# krajBB-Moj_i__Matej2_2.net
KiCad netlist of a schematic drawn in EAGLE
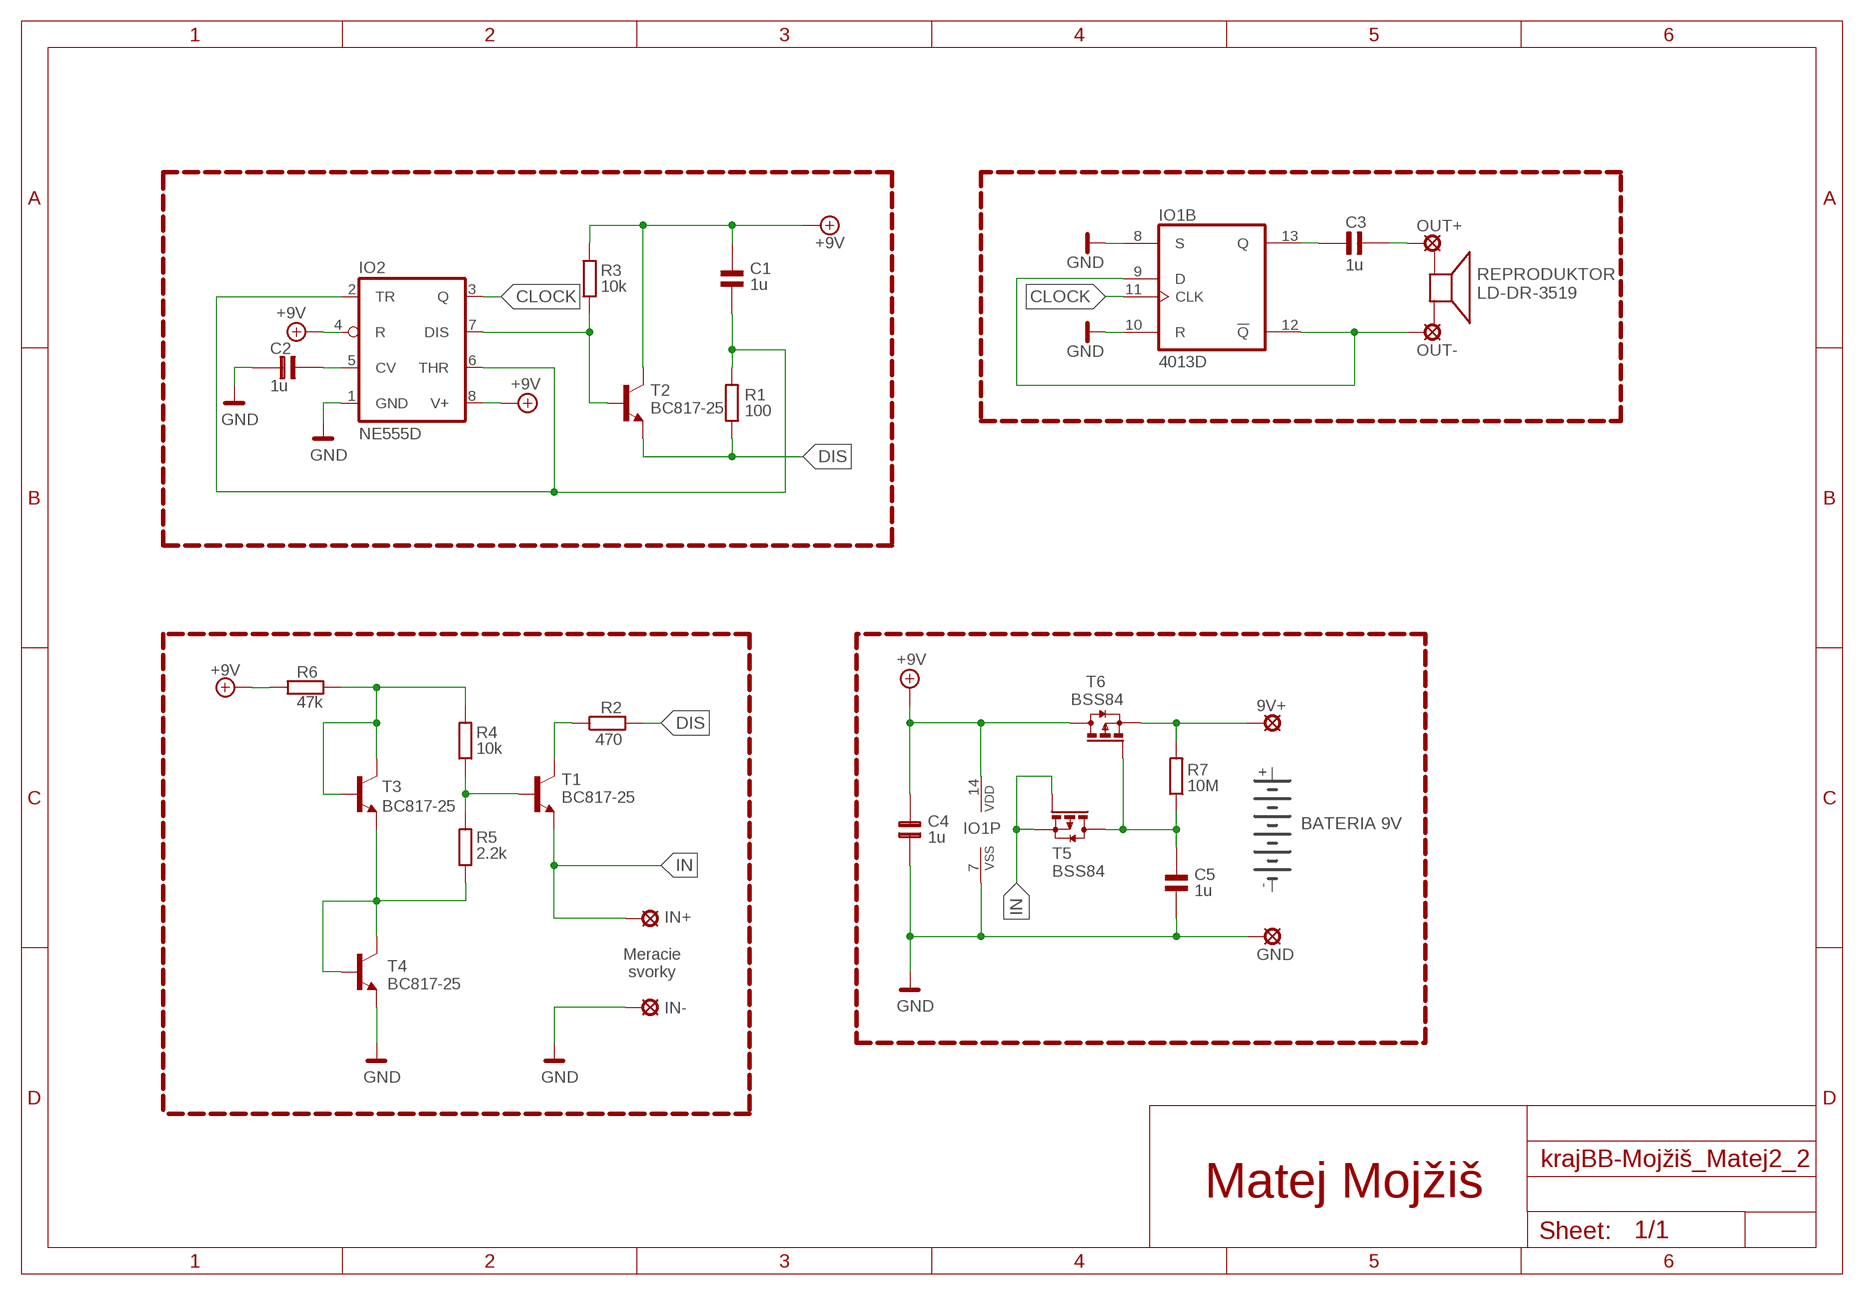
[diagram p0: schematic, sheet 1]

(export (version "E")
  (design (tool "Eeschema 10.0.6"))
  (components
    (comp (ref "9V+")
      (value "SMD3X3")
      (footprint "eagle-import:SMD3X3")
      (libsource (lib "eagle-import") (part "SMD3X3"))
    )
    (comp (ref "C1")
      (value "1u")
      (footprint "eagle-import:1206")
      (libsource (lib "eagle-import") (part "C1206TOP"))
    )
    (comp (ref "C2")
      (value "1u")
      (footprint "eagle-import:1206")
      (libsource (lib "eagle-import") (part "C1206TOP"))
    )
    (comp (ref "C3")
      (value "1u")
      (footprint "eagle-import:1206")
      (libsource (lib "eagle-import") (part "C1206TOP"))
    )
    (comp (ref "C4")
      (value "1u")
      (footprint "eagle-import:1206")
      (libsource (lib "eagle-import") (part "C1206TOP"))
    )
    (comp (ref "C5")
      (value "1u")
      (footprint "eagle-import:1206")
      (libsource (lib "eagle-import") (part "C1206TOP"))
    )
    (comp (ref "GND")
      (value "SMD3X3")
      (footprint "eagle-import:SMD3X3")
      (libsource (lib "eagle-import") (part "SMD3X3"))
    )
    (comp (ref "IN+")
      (value "SMD3X3")
      (footprint "eagle-import:SMD3X3")
      (libsource (lib "eagle-import") (part "SMD3X3"))
    )
    (comp (ref "IN-")
      (value "SMD3X3")
      (footprint "eagle-import:SMD3X3")
      (libsource (lib "eagle-import") (part "SMD3X3"))
    )
    (comp (ref "IO1")
      (value "4013D")
      (footprint "eagle-import:SO14")
      (libsource (lib "eagle-import") (part "4013D"))
    )
    (comp (ref "IO2")
      (value "NE555D")
      (footprint "eagle-import:SO08")
      (libsource (lib "eagle-import") (part "555DNE"))
    )
    (comp (ref "OUT+")
      (value "SMD3X3")
      (footprint "eagle-import:SMD3X3")
      (libsource (lib "eagle-import") (part "SMD3X3"))
    )
    (comp (ref "OUT-")
      (value "SMD3X3")
      (footprint "eagle-import:SMD3X3")
      (libsource (lib "eagle-import") (part "SMD3X3"))
    )
    (comp (ref "R1")
      (value "100")
      (footprint "eagle-import:1206")
      (libsource (lib "eagle-import") (part "R1206TOP"))
    )
    (comp (ref "R2")
      (value "470")
      (footprint "eagle-import:1206")
      (libsource (lib "eagle-import") (part "R1206TOP"))
    )
    (comp (ref "R3")
      (value "10k")
      (footprint "eagle-import:1206")
      (libsource (lib "eagle-import") (part "R1206TOP"))
    )
    (comp (ref "R4")
      (value "10k")
      (footprint "eagle-import:1206")
      (libsource (lib "eagle-import") (part "R1206TOP"))
    )
    (comp (ref "R5")
      (value "2.2k")
      (footprint "eagle-import:1206")
      (libsource (lib "eagle-import") (part "R1206TOP"))
    )
    (comp (ref "R6")
      (value "47k")
      (footprint "eagle-import:1206")
      (libsource (lib "eagle-import") (part "R1206TOP"))
    )
    (comp (ref "R7")
      (value "10M")
      (footprint "eagle-import:1206")
      (libsource (lib "eagle-import") (part "R1206TOP"))
    )
    (comp (ref "REPRODUKTOR")
      (value "LD-DR-3519")
      (footprint "eagle-import:LD-DR-3519")
      (libsource (lib "eagle-import") (part "LD-DR-3519"))
    )
    (comp (ref "T1")
      (value "BC817-25")
      (footprint "eagle-import:SOT23-BEC")
      (libsource (lib "eagle-import") (part "BC817SMD-25"))
    )
    (comp (ref "T2")
      (value "BC817-25")
      (footprint "eagle-import:SOT23-BEC")
      (libsource (lib "eagle-import") (part "BC817SMD-25"))
    )
    (comp (ref "T3")
      (value "BC817-25")
      (footprint "eagle-import:SOT23-BEC")
      (libsource (lib "eagle-import") (part "BC817SMD-25"))
    )
    (comp (ref "T4")
      (value "BC817-25")
      (footprint "eagle-import:SOT23-BEC")
      (libsource (lib "eagle-import") (part "BC817SMD-25"))
    )
    (comp (ref "T5")
      (value "BSS84")
      (footprint "eagle-import:SOT23")
      (libsource (lib "eagle-import") (part "BSS84"))
    )
    (comp (ref "T6")
      (value "BSS84")
      (footprint "eagle-import:SOT23")
      (libsource (lib "eagle-import") (part "BSS84"))
    )
    (comp (ref "U$1")
      (value "9VBATTERY")
      (footprint "eagle-import:9VBATTERY")
      (libsource (lib "eagle-import") (part "9VBATTERY"))
    )
  )
  (nets
    (net (code "1") (name "+9V") (class "Default")
      (node (ref "C1") (pin "2") (pinfunction "2_2") (pintype "passive"))
      (node (ref "C4") (pin "2") (pinfunction "2_2") (pintype "passive"))
      (node (ref "IO1") (pin "14") (pinfunction "VDD_14") (pintype "power_in"))
      (node (ref "IO2") (pin "4") (pinfunction "R_4") (pintype "input"))
      (node (ref "IO2") (pin "8") (pinfunction "V+_8") (pintype "power_in"))
      (node (ref "R3") (pin "2") (pinfunction "2_2") (pintype "passive"))
      (node (ref "R6") (pin "2") (pinfunction "2_2") (pintype "passive"))
      (node (ref "T2") (pin "C") (pinfunction "C_C") (pintype "passive"))
      (node (ref "T6") (pin "3") (pinfunction "D_3") (pintype "passive"))
    )
    (net (code "2") (name "CLOCK") (class "Default")
      (node (ref "IO1") (pin "11") (pinfunction "CLK_11") (pintype "input"))
      (node (ref "IO2") (pin "3") (pinfunction "Q_3") (pintype "output"))
    )
    (net (code "3") (name "DIS") (class "Default")
      (node (ref "R1") (pin "1") (pinfunction "1_1") (pintype "passive"))
      (node (ref "R2") (pin "2") (pinfunction "2_2") (pintype "passive"))
      (node (ref "T2") (pin "E") (pinfunction "E_E") (pintype "passive"))
    )
    (net (code "4") (name "GND") (class "Default")
      (node (ref "C2") (pin "1") (pinfunction "1_1") (pintype "passive"))
      (node (ref "C4") (pin "1") (pinfunction "1_1") (pintype "passive"))
      (node (ref "C5") (pin "1") (pinfunction "1_1") (pintype "passive"))
      (node (ref "GND") (pin "P$1") (pinfunction "MP_P$1") (pintype "passive"))
      (node (ref "IN-") (pin "P$1") (pinfunction "MP_P$1") (pintype "passive"))
      (node (ref "IO1") (pin "10") (pinfunction "R_10") (pintype "input"))
      (node (ref "IO1") (pin "7") (pinfunction "VSS_7") (pintype "power_in"))
      (node (ref "IO1") (pin "8") (pinfunction "S_8") (pintype "input"))
      (node (ref "IO2") (pin "1") (pinfunction "GND_1") (pintype "power_in"))
      (node (ref "T4") (pin "E") (pinfunction "E_E") (pintype "passive"))
    )
    (net (code "5") (name "IN") (class "Default")
      (node (ref "IN+") (pin "P$1") (pinfunction "MP_P$1") (pintype "passive"))
      (node (ref "T1") (pin "E") (pinfunction "E_E") (pintype "passive"))
      (node (ref "T5") (pin "1") (pinfunction "G_1") (pintype "passive"))
      (node (ref "T5") (pin "2") (pinfunction "S_2") (pintype "passive"))
    )
    (net (code "6") (name "Net-(9V+-MP)") (class "Default")
      (node (ref "9V+") (pin "P$1") (pinfunction "MP_P$1") (pintype "passive"))
      (node (ref "R7") (pin "2") (pinfunction "2_2") (pintype "passive"))
      (node (ref "T6") (pin "2") (pinfunction "S_2") (pintype "passive"))
    )
    (net (code "7") (name "Net-(IO1B-D)") (class "Default")
      (node (ref "IO1") (pin "12") (pinfunction "~{Q}_12") (pintype "output"))
      (node (ref "IO1") (pin "9") (pinfunction "D_9") (pintype "input"))
      (node (ref "OUT-") (pin "P$1") (pinfunction "MP_P$1") (pintype "passive"))
    )
    (net (code "8") (name "Net-(IO1B-Q)") (class "Default")
      (node (ref "C3") (pin "1") (pinfunction "1_1") (pintype "passive"))
      (node (ref "IO1") (pin "13") (pinfunction "Q_13") (pintype "output"))
    )
    (net (code "9") (name "Net-(IO2-CV)") (class "Default")
      (node (ref "C2") (pin "2") (pinfunction "2_2") (pintype "passive"))
      (node (ref "IO2") (pin "5") (pinfunction "CV_5") (pintype "input"))
    )
    (net (code "10") (name "Net-(IO2-DIS)") (class "Default")
      (node (ref "IO2") (pin "7") (pinfunction "DIS_7") (pintype "input"))
      (node (ref "R3") (pin "1") (pinfunction "1_1") (pintype "passive"))
      (node (ref "T2") (pin "B") (pinfunction "B_B") (pintype "passive"))
    )
    (net (code "11") (name "Net-(IO2-THR)") (class "Default")
      (node (ref "C1") (pin "1") (pinfunction "1_1") (pintype "passive"))
      (node (ref "IO2") (pin "2") (pinfunction "TR_2") (pintype "input"))
      (node (ref "IO2") (pin "6") (pinfunction "THR_6") (pintype "input"))
      (node (ref "R1") (pin "2") (pinfunction "2_2") (pintype "passive"))
    )
    (net (code "12") (name "Net-(OUT+-MP)") (class "Default")
      (node (ref "C3") (pin "2") (pinfunction "2_2") (pintype "passive"))
      (node (ref "OUT+") (pin "P$1") (pinfunction "MP_P$1") (pintype "passive"))
    )
    (net (code "13") (name "Net-(R2-Pad1)") (class "Default")
      (node (ref "R2") (pin "1") (pinfunction "1_1") (pintype "passive"))
      (node (ref "T1") (pin "C") (pinfunction "C_C") (pintype "passive"))
    )
    (net (code "14") (name "Net-(R4-Pad1)") (class "Default")
      (node (ref "R4") (pin "1") (pinfunction "1_1") (pintype "passive"))
      (node (ref "R5") (pin "2") (pinfunction "2_2") (pintype "passive"))
      (node (ref "T1") (pin "B") (pinfunction "B_B") (pintype "passive"))
    )
    (net (code "15") (name "Net-(R4-Pad2)") (class "Default")
      (node (ref "R4") (pin "2") (pinfunction "2_2") (pintype "passive"))
      (node (ref "R6") (pin "1") (pinfunction "1_1") (pintype "passive"))
      (node (ref "T3") (pin "B") (pinfunction "B_B") (pintype "passive"))
      (node (ref "T3") (pin "C") (pinfunction "C_C") (pintype "passive"))
    )
    (net (code "16") (name "Net-(R5-Pad1)") (class "Default")
      (node (ref "R5") (pin "1") (pinfunction "1_1") (pintype "passive"))
      (node (ref "T3") (pin "E") (pinfunction "E_E") (pintype "passive"))
      (node (ref "T4") (pin "B") (pinfunction "B_B") (pintype "passive"))
      (node (ref "T4") (pin "C") (pinfunction "C_C") (pintype "passive"))
    )
    (net (code "17") (name "Net-(T5-D)") (class "Default")
      (node (ref "C5") (pin "2") (pinfunction "2_2") (pintype "passive"))
      (node (ref "R7") (pin "1") (pinfunction "1_1") (pintype "passive"))
      (node (ref "T5") (pin "3") (pinfunction "D_3") (pintype "passive"))
      (node (ref "T6") (pin "1") (pinfunction "G_1") (pintype "passive"))
    )
    (net (code "18") (name "unconnected-(REPRODUKTOR-1-PadP$1)") (class "Default")
      (node (ref "REPRODUKTOR") (pin "P$1") (pinfunction "1_P$1") (pintype "passive"))
    )
    (net (code "19") (name "unconnected-(REPRODUKTOR-2-PadP$2)") (class "Default")
      (node (ref "REPRODUKTOR") (pin "P$2") (pinfunction "2_P$2") (pintype "passive"))
    )
  )
)
